# DWM1000_rev3_1_5mmdrill.net
KiCad netlist of a schematic drawn in EAGLE
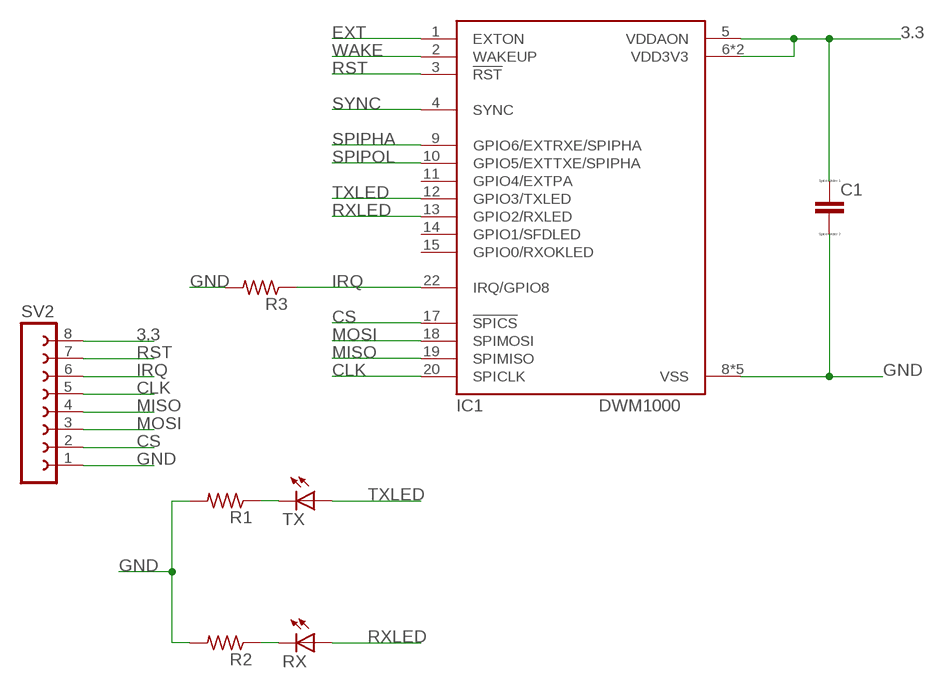
[diagram p0: schematic, sheet 1]

(export (version "E")
  (design (tool "Eeschema 10.0.6"))
  (components
    (comp (ref "C1")
      (value "CC1206")
      (footprint "eagle-import:C1206")
      (libsource (lib "eagle-import") (part "CC1206"))
    )
    (comp (ref "IC1")
      (value "DWM1000")
      (footprint "eagle-import:DWM1000")
      (libsource (lib "eagle-import") (part "DWM1000"))
    )
    (comp (ref "R1")
      (value "R-US_M0805")
      (footprint "eagle-import:M0805")
      (libsource (lib "eagle-import") (part "R-US_M0805"))
    )
    (comp (ref "R2")
      (value "R-US_M0805")
      (footprint "eagle-import:M0805")
      (libsource (lib "eagle-import") (part "R-US_M0805"))
    )
    (comp (ref "R3")
      (value "R-US_M0805")
      (footprint "eagle-import:M0805")
      (libsource (lib "eagle-import") (part "R-US_M0805"))
    )
    (comp (ref "RX")
      (value "LEDKA-3528ASYC")
      (footprint "eagle-import:KA-3528ASYC")
      (libsource (lib "eagle-import") (part "LEDKA-3528ASYC"))
    )
    (comp (ref "SV2")
      (value "FE08-1")
      (footprint "eagle-import:FE08")
      (libsource (lib "eagle-import") (part "FE08-1"))
    )
    (comp (ref "TX")
      (value "LEDKA-3528ASYC")
      (footprint "eagle-import:KA-3528ASYC")
      (libsource (lib "eagle-import") (part "LEDKA-3528ASYC"))
    )
  )
  (nets
    (net (code "1") (name "/3.3") (class "Default")
      (node (ref "C1") (pin "1") (pinfunction "1_1") (pintype "passive"))
      (node (ref "IC1") (pin "5") (pinfunction "VDDAON_5") (pintype "bidirectional"))
      (node (ref "IC1") (pin "6") (pinfunction "VDD3V3_6") (pintype "bidirectional"))
      (node (ref "IC1") (pin "7") (pinfunction "VDD3V3_7") (pintype "bidirectional"))
      (node (ref "SV2") (pin "8") (pinfunction "8_8") (pintype "passive"))
    )
    (net (code "2") (name "/CLK") (class "Default")
      (node (ref "IC1") (pin "20") (pinfunction "SPICLK_20") (pintype "bidirectional"))
      (node (ref "SV2") (pin "5") (pinfunction "5_5") (pintype "passive"))
    )
    (net (code "3") (name "/CS") (class "Default")
      (node (ref "IC1") (pin "17") (pinfunction "~{SPICS}_17") (pintype "bidirectional"))
      (node (ref "SV2") (pin "2") (pinfunction "2_2") (pintype "passive"))
    )
    (net (code "4") (name "/EXT") (class "Default")
      (node (ref "IC1") (pin "1") (pinfunction "EXTON_1") (pintype "bidirectional"))
    )
    (net (code "5") (name "/GND") (class "Default")
      (node (ref "C1") (pin "2") (pinfunction "2_2") (pintype "passive"))
      (node (ref "IC1") (pin "16") (pinfunction "VSS_16") (pintype "bidirectional"))
      (node (ref "IC1") (pin "21") (pinfunction "VSS_21") (pintype "bidirectional"))
      (node (ref "IC1") (pin "23") (pinfunction "VSS_23") (pintype "bidirectional"))
      (node (ref "IC1") (pin "24") (pinfunction "VSS_24") (pintype "bidirectional"))
      (node (ref "IC1") (pin "8") (pinfunction "VSS_8") (pintype "bidirectional"))
      (node (ref "R1") (pin "2") (pinfunction "2_2") (pintype "passive"))
      (node (ref "R2") (pin "2") (pinfunction "2_2") (pintype "passive"))
      (node (ref "R3") (pin "2") (pinfunction "2_2") (pintype "passive"))
      (node (ref "SV2") (pin "1") (pinfunction "1_1") (pintype "passive"))
    )
    (net (code "6") (name "/IRQ") (class "Default")
      (node (ref "IC1") (pin "22") (pinfunction "IRQ/GPIO8_22") (pintype "bidirectional"))
      (node (ref "R3") (pin "1") (pinfunction "1_1") (pintype "passive"))
      (node (ref "SV2") (pin "6") (pinfunction "6_6") (pintype "passive"))
    )
    (net (code "7") (name "/MISO") (class "Default")
      (node (ref "IC1") (pin "19") (pinfunction "SPIMISO_19") (pintype "bidirectional"))
      (node (ref "SV2") (pin "4") (pinfunction "4_4") (pintype "passive"))
    )
    (net (code "8") (name "/MOSI") (class "Default")
      (node (ref "IC1") (pin "18") (pinfunction "SPIMOSI_18") (pintype "bidirectional"))
      (node (ref "SV2") (pin "3") (pinfunction "3_3") (pintype "passive"))
    )
    (net (code "9") (name "/RST") (class "Default")
      (node (ref "IC1") (pin "3") (pinfunction "~{RST}_3") (pintype "bidirectional"))
      (node (ref "SV2") (pin "7") (pinfunction "7_7") (pintype "passive"))
    )
    (net (code "10") (name "/RXLED") (class "Default")
      (node (ref "IC1") (pin "13") (pinfunction "GPIO2/RXLED_13") (pintype "bidirectional"))
      (node (ref "RX") (pin "A") (pinfunction "A_A") (pintype "passive"))
    )
    (net (code "11") (name "/SPIPHA") (class "Default")
      (node (ref "IC1") (pin "9") (pinfunction "GPIO6/EXTRXE/SPIPHA_9") (pintype "bidirectional"))
    )
    (net (code "12") (name "/SPIPOL") (class "Default")
      (node (ref "IC1") (pin "10") (pinfunction "GPIO5/EXTTXE/SPIPHA_10") (pintype "bidirectional"))
    )
    (net (code "13") (name "/SYNC") (class "Default")
      (node (ref "IC1") (pin "4") (pinfunction "SYNC_4") (pintype "bidirectional"))
    )
    (net (code "14") (name "/TXLED") (class "Default")
      (node (ref "IC1") (pin "12") (pinfunction "GPIO3/TXLED_12") (pintype "bidirectional"))
      (node (ref "TX") (pin "A") (pinfunction "A_A") (pintype "passive"))
    )
    (net (code "15") (name "/WAKE") (class "Default")
      (node (ref "IC1") (pin "2") (pinfunction "WAKEUP_2") (pintype "bidirectional"))
    )
    (net (code "16") (name "Net-(R1-Pad1)") (class "Default")
      (node (ref "R1") (pin "1") (pinfunction "1_1") (pintype "passive"))
      (node (ref "TX") (pin "C") (pinfunction "C_C") (pintype "passive"))
    )
    (net (code "17") (name "Net-(R2-Pad1)") (class "Default")
      (node (ref "R2") (pin "1") (pinfunction "1_1") (pintype "passive"))
      (node (ref "RX") (pin "C") (pinfunction "C_C") (pintype "passive"))
    )
    (net (code "18") (name "unconnected-(IC1-GPIO0{slash}RXOKLED-Pad15)") (class "Default")
      (node (ref "IC1") (pin "15") (pinfunction "GPIO0/RXOKLED_15") (pintype "bidirectional"))
    )
    (net (code "19") (name "unconnected-(IC1-GPIO1{slash}SFDLED-Pad14)") (class "Default")
      (node (ref "IC1") (pin "14") (pinfunction "GPIO1/SFDLED_14") (pintype "bidirectional"))
    )
    (net (code "20") (name "unconnected-(IC1-GPIO4{slash}EXTPA-Pad11)") (class "Default")
      (node (ref "IC1") (pin "11") (pinfunction "GPIO4/EXTPA_11") (pintype "bidirectional"))
    )
  )
)
